# ArduOSD_Simple2222.net
KiCad netlist of a schematic drawn in EAGLE
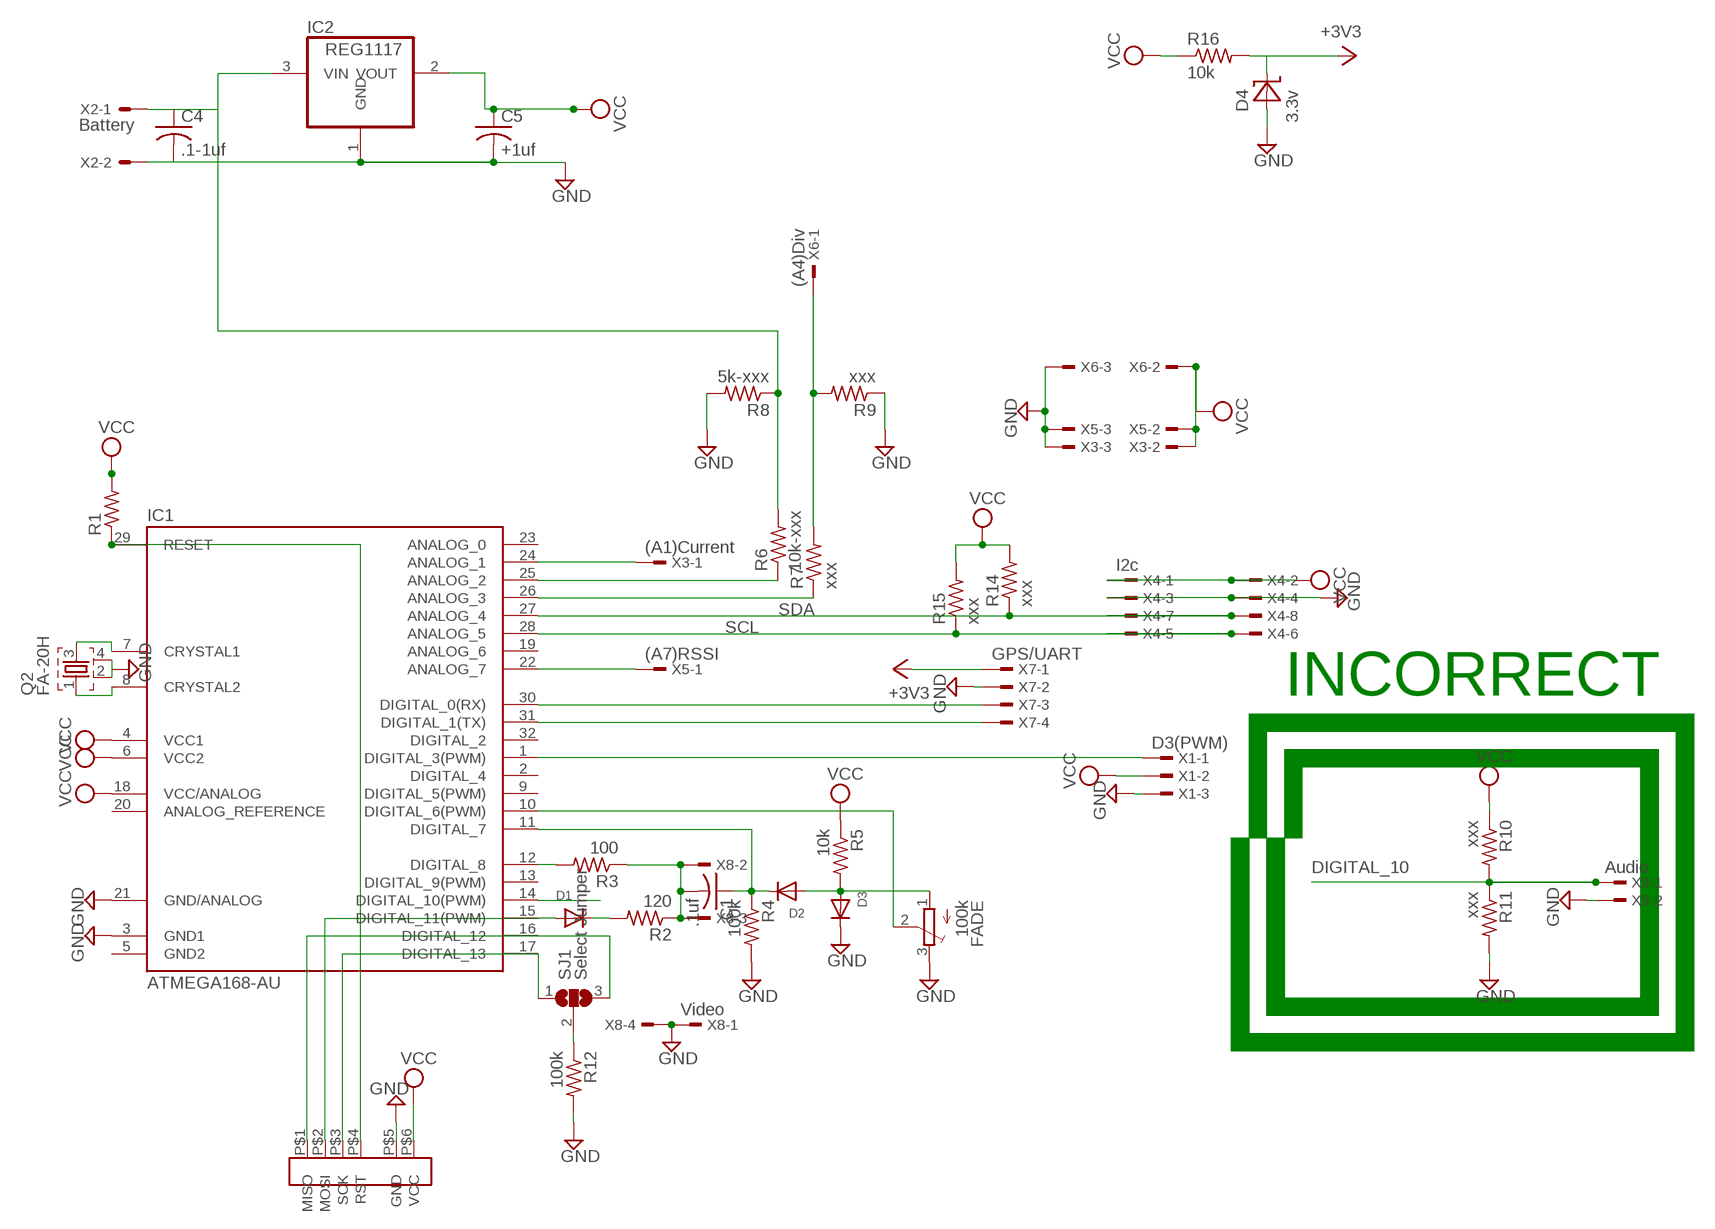
[diagram p0: schematic, sheet 1]

(export (version "E")
  (design (tool "Eeschema 10.0.6"))
  (components
    (comp (ref "C1")
      (value ".1uf")
      (footprint "eagle-import:C0805K")
      (libsource (lib "eagle-import") (part "C-USC0805K"))
    )
    (comp (ref "C4")
      (value ".1-1uf")
      (footprint "eagle-import:C0805K")
      (libsource (lib "eagle-import") (part "C-USC0805K"))
    )
    (comp (ref "C5")
      (value "+1uf")
      (footprint "eagle-import:C0805K")
      (libsource (lib "eagle-import") (part "C-USC0805K"))
    )
    (comp (ref "D1")
      (value "DIODESOT23_WAVE")
      (footprint "eagle-import:SOT23-W")
      (libsource (lib "eagle-import") (part "DIODESOT23_WAVE"))
    )
    (comp (ref "D2")
      (value "DIODESOT23_WAVE")
      (footprint "eagle-import:SOT23-W")
      (libsource (lib "eagle-import") (part "DIODESOT23_WAVE"))
    )
    (comp (ref "D3")
      (value "DIODESOT23_WAVE")
      (footprint "eagle-import:SOT23-W")
      (libsource (lib "eagle-import") (part "DIODESOT23_WAVE"))
    )
    (comp (ref "D4")
      (value "3.3v")
      (footprint "eagle-import:SOD-123")
      (libsource (lib "eagle-import") (part "ZENER_SOD123"))
    )
    (comp (ref "FADE")
      (value "100k")
      (footprint "eagle-import:TC33X")
      (libsource (lib "eagle-import") (part "TRIMPOTTC33X"))
    )
    (comp (ref "IC1")
      (value "ATMEGA168-AU")
      (footprint "eagle-import:TQFP32-08")
      (libsource (lib "eagle-import") (part "ATMEGA168-AU"))
    )
    (comp (ref "IC2")
      (value "REG1117")
      (footprint "eagle-import:SOT223")
      (libsource (lib "eagle-import") (part "REG1117"))
    )
    (comp (ref "Q2")
      (value "FA-20H")
      (footprint "eagle-import:FA-20H")
      (libsource (lib "eagle-import") (part "FA-20H"))
    )
    (comp (ref "R1")
      (value "R-US_R0805")
      (footprint "eagle-import:R0805")
      (libsource (lib "eagle-import") (part "R-US_R0805"))
    )
    (comp (ref "R2")
      (value "120")
      (footprint "eagle-import:R0805")
      (libsource (lib "eagle-import") (part "R-US_R0805"))
    )
    (comp (ref "R3")
      (value "100")
      (footprint "eagle-import:R0805")
      (libsource (lib "eagle-import") (part "R-US_R0805"))
    )
    (comp (ref "R4")
      (value "100k")
      (footprint "eagle-import:R0805")
      (libsource (lib "eagle-import") (part "R-US_R0805"))
    )
    (comp (ref "R5")
      (value "10k")
      (footprint "eagle-import:R0805")
      (libsource (lib "eagle-import") (part "R-US_R0805"))
    )
    (comp (ref "R6")
      (value "10k-xxx")
      (footprint "eagle-import:R0805")
      (libsource (lib "eagle-import") (part "R-US_R0805"))
    )
    (comp (ref "R7")
      (value "xxx")
      (footprint "eagle-import:R0805")
      (libsource (lib "eagle-import") (part "R-US_R0805"))
    )
    (comp (ref "R8")
      (value "5k-xxx")
      (footprint "eagle-import:R0805")
      (libsource (lib "eagle-import") (part "R-US_R0805"))
    )
    (comp (ref "R9")
      (value "xxx")
      (footprint "eagle-import:R0805")
      (libsource (lib "eagle-import") (part "R-US_R0805"))
    )
    (comp (ref "R10")
      (value "xxx")
      (footprint "eagle-import:R0805")
      (libsource (lib "eagle-import") (part "R-US_R0805"))
    )
    (comp (ref "R11")
      (value "xxx")
      (footprint "eagle-import:R0805")
      (libsource (lib "eagle-import") (part "R-US_R0805"))
    )
    (comp (ref "R12")
      (value "100k")
      (footprint "eagle-import:R0805")
      (libsource (lib "eagle-import") (part "R-US_R0805"))
    )
    (comp (ref "R14")
      (value "xxx")
      (footprint "eagle-import:R0805")
      (libsource (lib "eagle-import") (part "R-US_R0805"))
    )
    (comp (ref "R15")
      (value "xxx")
      (footprint "eagle-import:R0805")
      (libsource (lib "eagle-import") (part "R-US_R0805"))
    )
    (comp (ref "R16")
      (value "10k")
      (footprint "eagle-import:R0805")
      (libsource (lib "eagle-import") (part "R-US_R0805"))
    )
    (comp (ref "SJ1")
      (value "Select Jumper")
      (footprint "eagle-import:SJ_2")
      (libsource (lib "eagle-import") (part "SJ2W"))
    )
    (comp (ref "U$1")
      (value "LIN_ISP")
      (footprint "eagle-import:LINEAR_ISP")
      (libsource (lib "eagle-import") (part "LIN_ISP"))
    )
    (comp (ref "X1")
      (value "D3(PWM)")
      (footprint "eagle-import:TSW-103-02-S-S")
      (fields (field (name "OC_FARNELL") "unknown") (field (name "OC_NEWARK") "unknown"))
      (libsource (lib "eagle-import") (part "TSW-103-02-S-S"))
    )
    (comp (ref "X2")
      (value "Battery")
      (footprint "eagle-import:22-23-2021")
      (fields (field (name "MF") "MOLEX") (field (name "MPN") "22-23-2021"))
      (libsource (lib "eagle-import") (part "22-23-2021"))
    )
    (comp (ref "X3")
      (value "(A1)Current")
      (footprint "eagle-import:TSW-103-02-S-S")
      (libsource (lib "eagle-import") (part "TSW-103-02-S-S"))
    )
    (comp (ref "X4")
      (value "I2c")
      (footprint "eagle-import:TSW-104-02-S-D-RA")
      (libsource (lib "eagle-import") (part "TSW-104-02-S-D-RA"))
    )
    (comp (ref "X5")
      (value "(A7)RSSI")
      (footprint "eagle-import:TSW-103-02-S-S")
      (libsource (lib "eagle-import") (part "TSW-103-02-S-S"))
    )
    (comp (ref "X6")
      (value "(A4)Div")
      (footprint "eagle-import:TSW-103-02-S-S")
      (fields (field (name "OC_FARNELL") "unknown") (field (name "OC_NEWARK") "unknown"))
      (libsource (lib "eagle-import") (part "TSW-103-02-S-S"))
    )
    (comp (ref "X7")
      (value "GPS/UART")
      (footprint "eagle-import:TSW-104-02-S-S-RA")
      (libsource (lib "eagle-import") (part "TSW-104-02-S-S-RA"))
    )
    (comp (ref "X8")
      (value "Video")
      (footprint "eagle-import:TSW-104-02-S-S-RA")
      (libsource (lib "eagle-import") (part "TSW-104-02-S-S-RA"))
    )
    (comp (ref "X9")
      (value "Audio")
      (footprint "eagle-import:TSW-102-02-S-S-RA")
      (fields (field (name "OC_FARNELL") "unknown") (field (name "OC_NEWARK") "unknown"))
      (libsource (lib "eagle-import") (part "TSW-102-02-S-S-RA"))
    )
  )
  (nets
    (net (code "1") (name "+3V3") (class "Default")
      (node (ref "D4") (pin "1") (pinfunction "C_1") (pintype "passive"))
      (node (ref "R16") (pin "2") (pinfunction "2_2") (pintype "passive"))
      (node (ref "X7") (pin "1") (pinfunction "1_1") (pintype "passive"))
    )
    (net (code "2") (name "/DIGITAL_10") (class "Default")
      (node (ref "IC1") (pin "14") (pinfunction "DIGITAL_10(PWM)_14") (pintype "bidirectional"))
      (node (ref "R10") (pin "2") (pinfunction "2_2") (pintype "passive"))
      (node (ref "R11") (pin "1") (pinfunction "1_1") (pintype "passive"))
      (node (ref "X9") (pin "1") (pinfunction "1_1") (pintype "passive"))
    )
    (net (code "3") (name "/GND2") (class "Default")
      (node (ref "IC1") (pin "5") (pinfunction "GND2_5") (pintype "power_in"))
    )
    (net (code "4") (name "/SCL") (class "Default")
      (node (ref "IC1") (pin "28") (pinfunction "ANALOG_5_28") (pintype "bidirectional"))
      (node (ref "R15") (pin "1") (pinfunction "1_1") (pintype "passive"))
      (node (ref "X4") (pin "5") (pinfunction "1_5") (pintype "passive"))
      (node (ref "X4") (pin "6") (pinfunction "1_6") (pintype "passive"))
    )
    (net (code "5") (name "/SDA") (class "Default")
      (node (ref "IC1") (pin "27") (pinfunction "ANALOG_4_27") (pintype "bidirectional"))
      (node (ref "R14") (pin "1") (pinfunction "1_1") (pintype "passive"))
      (node (ref "X4") (pin "7") (pinfunction "1_7") (pintype "passive"))
      (node (ref "X4") (pin "8") (pinfunction "1_8") (pintype "passive"))
    )
    (net (code "6") (name "GND") (class "Default")
      (node (ref "C4") (pin "2") (pinfunction "2_2") (pintype "passive"))
      (node (ref "C5") (pin "2") (pinfunction "2_2") (pintype "passive"))
      (node (ref "D3") (pin "3") (pinfunction "C_3") (pintype "passive"))
      (node (ref "D4") (pin "2") (pinfunction "A_2") (pintype "passive"))
      (node (ref "FADE") (pin "3") (pinfunction "E_3") (pintype "passive"))
      (node (ref "IC1") (pin "21") (pinfunction "GND/ANALOG_21") (pintype "power_in"))
      (node (ref "IC1") (pin "3") (pinfunction "GND1_3") (pintype "power_in"))
      (node (ref "IC2") (pin "1") (pinfunction "GND_1") (pintype "power_in"))
      (node (ref "Q2") (pin "2") (pinfunction "2_2") (pintype "passive"))
      (node (ref "Q2") (pin "4") (pinfunction "4_4") (pintype "passive"))
      (node (ref "R11") (pin "2") (pinfunction "2_2") (pintype "passive"))
      (node (ref "R12") (pin "2") (pinfunction "2_2") (pintype "passive"))
      (node (ref "R4") (pin "2") (pinfunction "2_2") (pintype "passive"))
      (node (ref "R8") (pin "2") (pinfunction "2_2") (pintype "passive"))
      (node (ref "R9") (pin "1") (pinfunction "1_1") (pintype "passive"))
      (node (ref "U$1") (pin "P$5") (pinfunction "GND_P$5") (pintype "bidirectional"))
      (node (ref "X1") (pin "3") (pinfunction "1_3") (pintype "passive"))
      (node (ref "X2") (pin "2") (pinfunction "S_2") (pintype "passive"))
      (node (ref "X3") (pin "3") (pinfunction "1_3") (pintype "passive"))
      (node (ref "X4") (pin "3") (pinfunction "1_3") (pintype "passive"))
      (node (ref "X4") (pin "4") (pinfunction "1_4") (pintype "passive"))
      (node (ref "X5") (pin "3") (pinfunction "1_3") (pintype "passive"))
      (node (ref "X6") (pin "3") (pinfunction "1_3") (pintype "passive"))
      (node (ref "X7") (pin "2") (pinfunction "1_2") (pintype "passive"))
      (node (ref "X8") (pin "1") (pinfunction "1_1") (pintype "passive"))
      (node (ref "X8") (pin "4") (pinfunction "1_4") (pintype "passive"))
      (node (ref "X9") (pin "2") (pinfunction "1_2") (pintype "passive"))
    )
    (net (code "7") (name "Net-(D1-A)") (class "Default")
      (node (ref "D1") (pin "1") (pinfunction "A_1") (pintype "passive"))
      (node (ref "IC1") (pin "15") (pinfunction "DIGITAL_11(PWM)_15") (pintype "bidirectional"))
      (node (ref "U$1") (pin "P$2") (pinfunction "MOSI_P$2") (pintype "bidirectional"))
    )
    (net (code "8") (name "Net-(D1-C)") (class "Default")
      (node (ref "D1") (pin "3") (pinfunction "C_3") (pintype "passive"))
      (node (ref "R2") (pin "2") (pinfunction "2_2") (pintype "passive"))
    )
    (net (code "9") (name "Net-(D2-A)") (class "Default")
      (node (ref "D2") (pin "1") (pinfunction "A_1") (pintype "passive"))
      (node (ref "D3") (pin "1") (pinfunction "A_1") (pintype "passive"))
      (node (ref "FADE") (pin "1") (pinfunction "A_1") (pintype "passive"))
      (node (ref "R5") (pin "2") (pinfunction "2_2") (pintype "passive"))
    )
    (net (code "10") (name "Net-(D2-C)") (class "Default")
      (node (ref "C1") (pin "1") (pinfunction "1_1") (pintype "passive"))
      (node (ref "D2") (pin "3") (pinfunction "C_3") (pintype "passive"))
      (node (ref "IC1") (pin "11") (pinfunction "DIGITAL_7_11") (pintype "bidirectional"))
      (node (ref "R4") (pin "1") (pinfunction "1_1") (pintype "passive"))
    )
    (net (code "11") (name "Net-(FADE-S)") (class "Default")
      (node (ref "FADE") (pin "2") (pinfunction "S_2") (pintype "passive"))
      (node (ref "IC1") (pin "10") (pinfunction "DIGITAL_6(PWM)_10") (pintype "bidirectional"))
    )
    (net (code "12") (name "Net-(IC1-ANALOG_1)") (class "Default")
      (node (ref "IC1") (pin "24") (pinfunction "ANALOG_1_24") (pintype "bidirectional"))
      (node (ref "X3") (pin "1") (pinfunction "1_1") (pintype "passive"))
    )
    (net (code "13") (name "Net-(IC1-ANALOG_2)") (class "Default")
      (node (ref "IC1") (pin "25") (pinfunction "ANALOG_2_25") (pintype "bidirectional"))
      (node (ref "R6") (pin "1") (pinfunction "1_1") (pintype "passive"))
    )
    (net (code "14") (name "Net-(IC1-ANALOG_3)") (class "Default")
      (node (ref "IC1") (pin "26") (pinfunction "ANALOG_3_26") (pintype "bidirectional"))
      (node (ref "R7") (pin "1") (pinfunction "1_1") (pintype "passive"))
    )
    (net (code "15") (name "Net-(IC1-ANALOG_7)") (class "Default")
      (node (ref "IC1") (pin "22") (pinfunction "ANALOG_7_22") (pintype "passive"))
      (node (ref "X5") (pin "1") (pinfunction "1_1") (pintype "passive"))
    )
    (net (code "16") (name "Net-(IC1-CRYSTAL1)") (class "Default")
      (node (ref "IC1") (pin "7") (pinfunction "CRYSTAL1_7") (pintype "bidirectional"))
      (node (ref "Q2") (pin "3") (pinfunction "3_3") (pintype "passive"))
    )
    (net (code "17") (name "Net-(IC1-CRYSTAL2)") (class "Default")
      (node (ref "IC1") (pin "8") (pinfunction "CRYSTAL2_8") (pintype "bidirectional"))
      (node (ref "Q2") (pin "1") (pinfunction "1_1") (pintype "passive"))
    )
    (net (code "18") (name "Net-(IC1-DIGITAL_0(RX))") (class "Default")
      (node (ref "IC1") (pin "30") (pinfunction "DIGITAL_0(RX)_30") (pintype "bidirectional"))
      (node (ref "X7") (pin "3") (pinfunction "1_3") (pintype "passive"))
    )
    (net (code "19") (name "Net-(IC1-DIGITAL_1(TX))") (class "Default")
      (node (ref "IC1") (pin "31") (pinfunction "DIGITAL_1(TX)_31") (pintype "bidirectional"))
      (node (ref "X7") (pin "4") (pinfunction "1_4") (pintype "passive"))
    )
    (net (code "20") (name "Net-(IC1-DIGITAL_3(PWM))") (class "Default")
      (node (ref "IC1") (pin "1") (pinfunction "DIGITAL_3(PWM)_1") (pintype "bidirectional"))
      (node (ref "X1") (pin "1") (pinfunction "1_1") (pintype "passive"))
    )
    (net (code "21") (name "Net-(IC1-DIGITAL_8)") (class "Default")
      (node (ref "IC1") (pin "12") (pinfunction "DIGITAL_8_12") (pintype "bidirectional"))
      (node (ref "R3") (pin "2") (pinfunction "2_2") (pintype "passive"))
    )
    (net (code "22") (name "Net-(IC1-DIGITAL_12)") (class "Default")
      (node (ref "IC1") (pin "16") (pinfunction "DIGITAL_12_16") (pintype "bidirectional"))
      (node (ref "SJ1") (pin "3") (pinfunction "3_3") (pintype "passive"))
      (node (ref "U$1") (pin "P$1") (pinfunction "MISO_P$1") (pintype "bidirectional"))
    )
    (net (code "23") (name "Net-(IC1-DIGITAL_13)") (class "Default")
      (node (ref "IC1") (pin "17") (pinfunction "DIGITAL_13_17") (pintype "bidirectional"))
      (node (ref "SJ1") (pin "1") (pinfunction "1_1") (pintype "passive"))
      (node (ref "U$1") (pin "P$3") (pinfunction "SCK_P$3") (pintype "bidirectional"))
    )
    (net (code "24") (name "Net-(IC1-RESET)") (class "Default")
      (node (ref "IC1") (pin "29") (pinfunction "RESET_29") (pintype "bidirectional"))
      (node (ref "R1") (pin "1") (pinfunction "1_1") (pintype "passive"))
      (node (ref "U$1") (pin "P$4") (pinfunction "RST_P$4") (pintype "bidirectional"))
    )
    (net (code "25") (name "Net-(IC2-VIN)") (class "Default")
      (node (ref "C4") (pin "1") (pinfunction "1_1") (pintype "passive"))
      (node (ref "IC2") (pin "3") (pinfunction "VIN_3") (pintype "input"))
      (node (ref "R6") (pin "2") (pinfunction "2_2") (pintype "passive"))
      (node (ref "R8") (pin "1") (pinfunction "1_1") (pintype "passive"))
      (node (ref "X2") (pin "1") (pinfunction "S_1") (pintype "passive"))
    )
    (net (code "26") (name "Net-(R7-Pad2)") (class "Default")
      (node (ref "R7") (pin "2") (pinfunction "2_2") (pintype "passive"))
      (node (ref "R9") (pin "2") (pinfunction "2_2") (pintype "passive"))
      (node (ref "X6") (pin "1") (pinfunction "1_1") (pintype "passive"))
    )
    (net (code "27") (name "Net-(R12-Pad1)") (class "Default")
      (node (ref "R12") (pin "1") (pinfunction "1_1") (pintype "passive"))
      (node (ref "SJ1") (pin "2") (pinfunction "2_2") (pintype "passive"))
    )
    (net (code "28") (name "Net-(X8B-1)") (class "Default")
      (node (ref "C1") (pin "2") (pinfunction "2_2") (pintype "passive"))
      (node (ref "R2") (pin "1") (pinfunction "1_1") (pintype "passive"))
      (node (ref "R3") (pin "1") (pinfunction "1_1") (pintype "passive"))
      (node (ref "X8") (pin "2") (pinfunction "1_2") (pintype "passive"))
      (node (ref "X8") (pin "3") (pinfunction "1_3") (pintype "passive"))
    )
    (net (code "29") (name "VCC") (class "Default")
      (node (ref "C5") (pin "1") (pinfunction "1_1") (pintype "passive"))
      (node (ref "IC1") (pin "18") (pinfunction "VCC/ANALOG_18") (pintype "passive"))
      (node (ref "IC1") (pin "4") (pinfunction "VCC1_4") (pintype "power_in"))
      (node (ref "IC1") (pin "6") (pinfunction "VCC2_6") (pintype "power_in"))
      (node (ref "IC2") (pin "2") (pinfunction "VOUT_2") (pintype "output"))
      (node (ref "R1") (pin "2") (pinfunction "2_2") (pintype "passive"))
      (node (ref "R10") (pin "1") (pinfunction "1_1") (pintype "passive"))
      (node (ref "R14") (pin "2") (pinfunction "2_2") (pintype "passive"))
      (node (ref "R15") (pin "2") (pinfunction "2_2") (pintype "passive"))
      (node (ref "R16") (pin "1") (pinfunction "1_1") (pintype "passive"))
      (node (ref "R5") (pin "1") (pinfunction "1_1") (pintype "passive"))
      (node (ref "U$1") (pin "P$6") (pinfunction "VCC_P$6") (pintype "bidirectional"))
      (node (ref "X1") (pin "2") (pinfunction "1_2") (pintype "passive"))
      (node (ref "X3") (pin "2") (pinfunction "1_2") (pintype "passive"))
      (node (ref "X4") (pin "1") (pinfunction "1_1") (pintype "passive"))
      (node (ref "X4") (pin "2") (pinfunction "1_2") (pintype "passive"))
      (node (ref "X5") (pin "2") (pinfunction "1_2") (pintype "passive"))
      (node (ref "X6") (pin "2") (pinfunction "1_2") (pintype "passive"))
    )
    (net (code "30") (name "unconnected-(IC1-ANALOG_0-Pad23)") (class "Default")
      (node (ref "IC1") (pin "23") (pinfunction "ANALOG_0_23") (pintype "bidirectional"))
    )
    (net (code "31") (name "unconnected-(IC1-ANALOG_6-Pad19)") (class "Default")
      (node (ref "IC1") (pin "19") (pinfunction "ANALOG_6_19") (pintype "passive"))
    )
    (net (code "32") (name "unconnected-(IC1-ANALOG_REFERENCE-Pad20)") (class "Default")
      (node (ref "IC1") (pin "20") (pinfunction "ANALOG_REFERENCE_20") (pintype "passive"))
    )
    (net (code "33") (name "unconnected-(IC1-DIGITAL_2-Pad32)") (class "Default")
      (node (ref "IC1") (pin "32") (pinfunction "DIGITAL_2_32") (pintype "bidirectional"))
    )
    (net (code "34") (name "unconnected-(IC1-DIGITAL_4-Pad2)") (class "Default")
      (node (ref "IC1") (pin "2") (pinfunction "DIGITAL_4_2") (pintype "bidirectional"))
    )
    (net (code "35") (name "unconnected-(IC1-DIGITAL_5(PWM)-Pad9)") (class "Default")
      (node (ref "IC1") (pin "9") (pinfunction "DIGITAL_5(PWM)_9") (pintype "bidirectional"))
    )
    (net (code "36") (name "unconnected-(IC1-DIGITAL_9(PWM)-Pad13)") (class "Default")
      (node (ref "IC1") (pin "13") (pinfunction "DIGITAL_9(PWM)_13") (pintype "bidirectional"))
    )
  )
)
